# atmega_fusebit_doctor_V2hOld.net
KiCad netlist of a schematic drawn in EAGLE
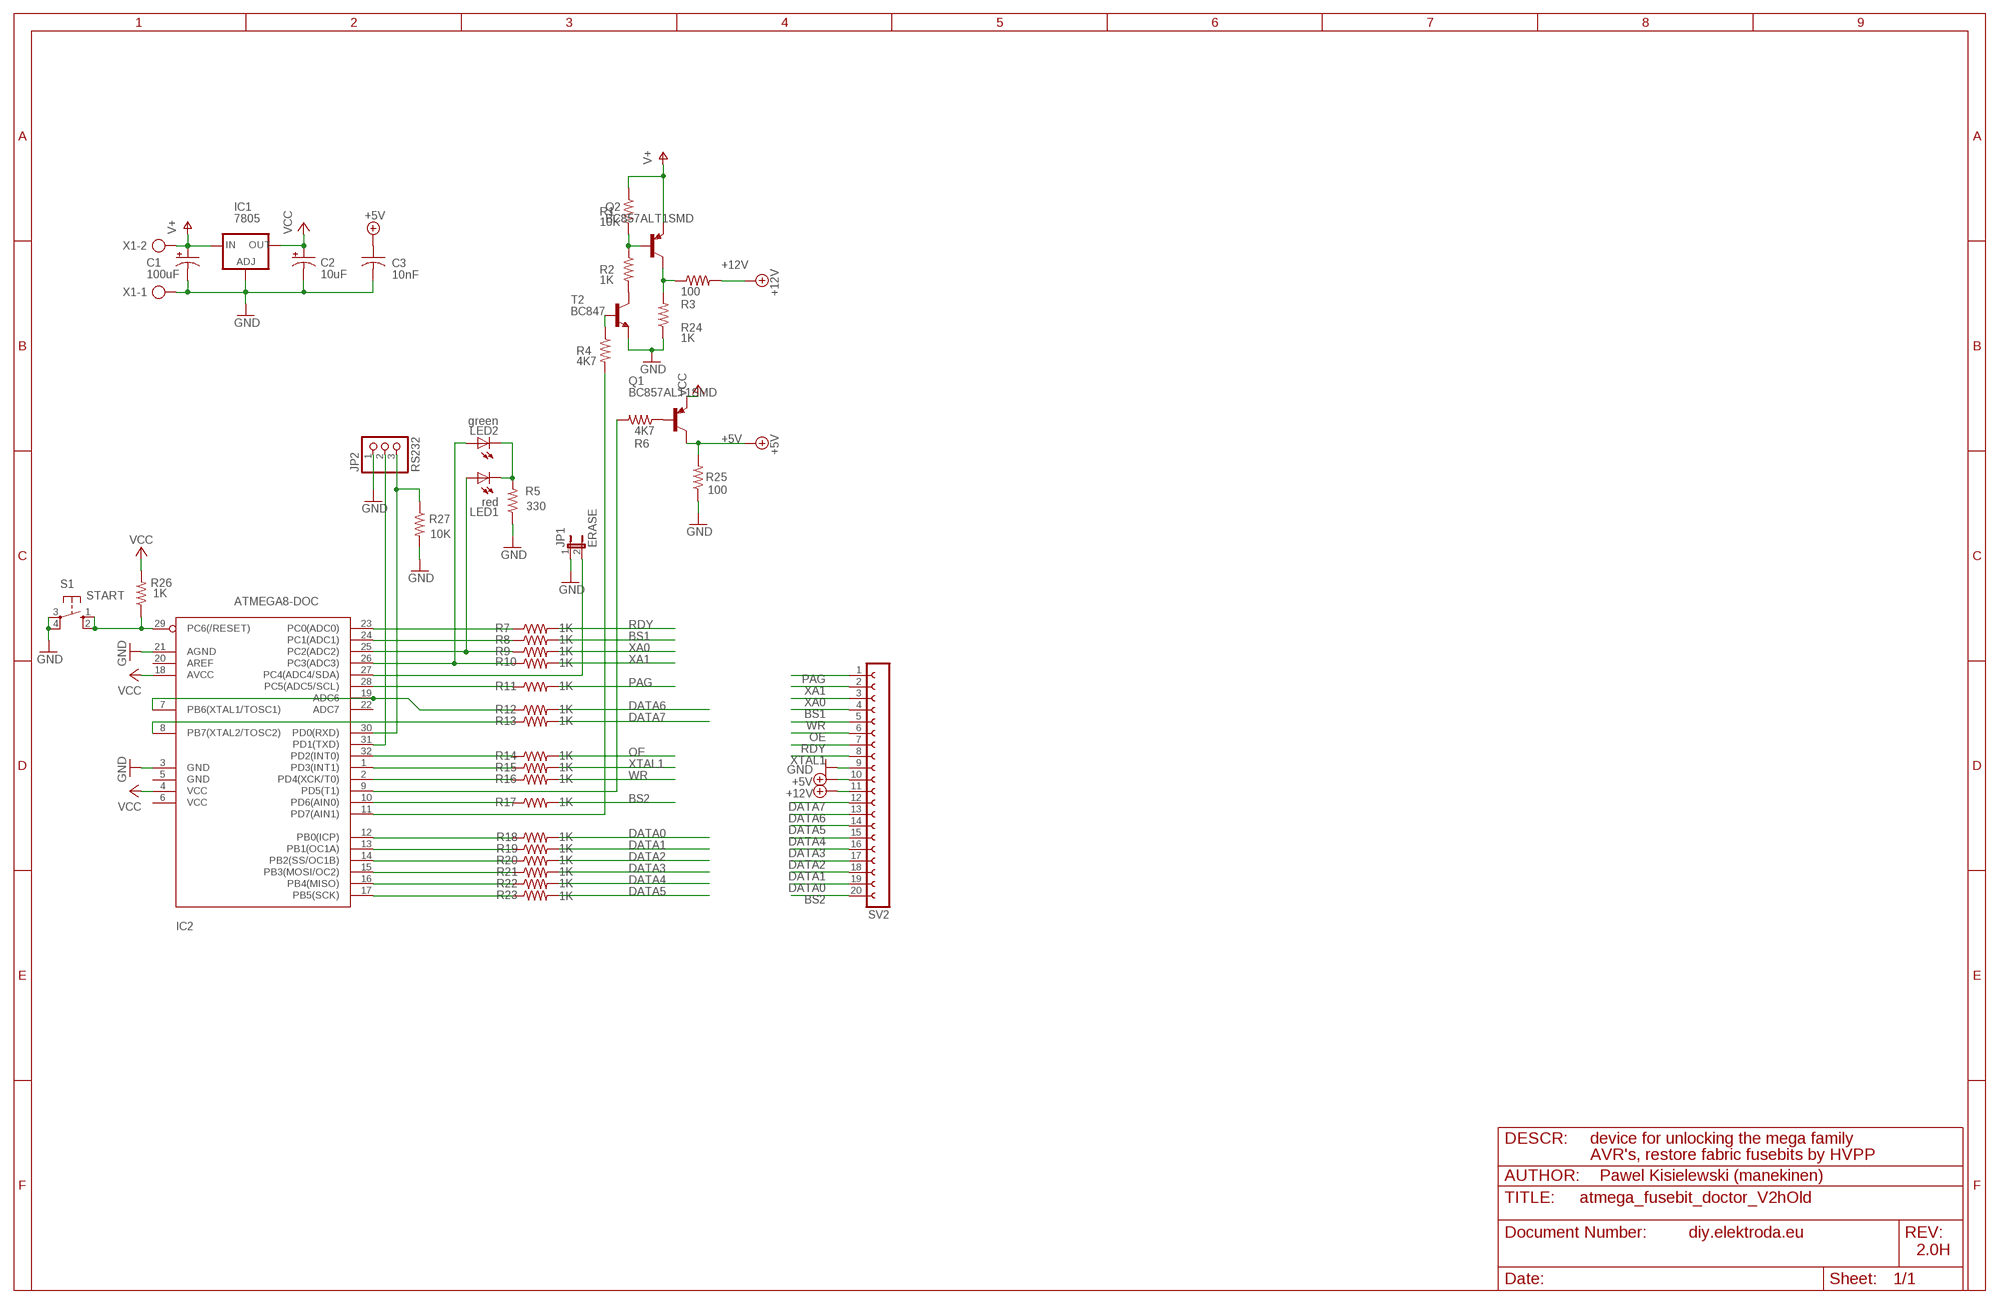
[diagram p0: schematic, sheet 1]

(export (version "E")
  (design (tool "Eeschema 10.0.6"))
  (components
    (comp (ref "C1")
      (value "100uF")
      (footprint "eagle-import:EIA3216")
      (libsource (lib "eagle-import") (part "CAP_POL1206"))
    )
    (comp (ref "C2")
      (value "10uF")
      (footprint "eagle-import:EIA3216")
      (libsource (lib "eagle-import") (part "CAP_POL1206"))
    )
    (comp (ref "C3")
      (value "10nF")
      (footprint "eagle-import:C0805")
      (libsource (lib "eagle-import") (part "C-USC0805"))
    )
    (comp (ref "IC1")
      (value "7805")
      (footprint "eagle-import:V-REG_DPACK")
      (libsource (lib "eagle-import") (part "V_REG_317DPACK"))
    )
    (comp (ref "IC2")
      (value "ATMEGA8-DOC")
      (footprint "eagle-import:TQFP32-08")
      (libsource (lib "eagle-import") (part "AVR-MEGA8-AI"))
    )
    (comp (ref "JP1")
      (value "ERASE")
      (footprint "eagle-import:JP1")
      (libsource (lib "eagle-import") (part "JP1E"))
    )
    (comp (ref "JP2")
      (value "RS232")
      (footprint "eagle-import:1X03")
      (libsource (lib "eagle-import") (part "PINHD-1X3"))
    )
    (comp (ref "LED1")
      (value "red")
      (footprint "eagle-import:SML0603")
      (libsource (lib "eagle-import") (part "LEDSML0603"))
    )
    (comp (ref "LED2")
      (value "green")
      (footprint "eagle-import:SML0603")
      (libsource (lib "eagle-import") (part "LEDSML0603"))
    )
    (comp (ref "Q1")
      (value "BC857ALT1SMD")
      (footprint "eagle-import:SOT23-BEC")
      (libsource (lib "eagle-import") (part "BC857SMDALT1"))
    )
    (comp (ref "Q2")
      (value "BC857ALT1SMD")
      (footprint "eagle-import:SOT23-BEC")
      (libsource (lib "eagle-import") (part "BC857SMDALT1"))
    )
    (comp (ref "R1")
      (value "10K")
      (footprint "eagle-import:R0805")
      (libsource (lib "eagle-import") (part "R-US_R0805"))
    )
    (comp (ref "R2")
      (value "1K")
      (footprint "eagle-import:R0805")
      (libsource (lib "eagle-import") (part "R-US_R0805"))
    )
    (comp (ref "R3")
      (value "100")
      (footprint "eagle-import:R0805")
      (libsource (lib "eagle-import") (part "R-US_R0805"))
    )
    (comp (ref "R4")
      (value "4K7")
      (footprint "eagle-import:R0805")
      (libsource (lib "eagle-import") (part "R-US_R0805"))
    )
    (comp (ref "R5")
      (value "330")
      (footprint "eagle-import:R0805")
      (libsource (lib "eagle-import") (part "R-US_R0805"))
    )
    (comp (ref "R6")
      (value "4K7")
      (footprint "eagle-import:R0805")
      (libsource (lib "eagle-import") (part "R-US_R0805"))
    )
    (comp (ref "R7")
      (value "1K")
      (footprint "eagle-import:R0805")
      (libsource (lib "eagle-import") (part "R-US_R0805"))
    )
    (comp (ref "R8")
      (value "1K")
      (footprint "eagle-import:R0805")
      (libsource (lib "eagle-import") (part "R-US_R0805"))
    )
    (comp (ref "R9")
      (value "1K")
      (footprint "eagle-import:R0805")
      (libsource (lib "eagle-import") (part "R-US_R0805"))
    )
    (comp (ref "R10")
      (value "1K")
      (footprint "eagle-import:R0805")
      (libsource (lib "eagle-import") (part "R-US_R0805"))
    )
    (comp (ref "R11")
      (value "1K")
      (footprint "eagle-import:R0805")
      (libsource (lib "eagle-import") (part "R-US_R0805"))
    )
    (comp (ref "R12")
      (value "1K")
      (footprint "eagle-import:R0805")
      (libsource (lib "eagle-import") (part "R-US_R0805"))
    )
    (comp (ref "R13")
      (value "1K")
      (footprint "eagle-import:R0805")
      (libsource (lib "eagle-import") (part "R-US_R0805"))
    )
    (comp (ref "R14")
      (value "1K")
      (footprint "eagle-import:R0805")
      (libsource (lib "eagle-import") (part "R-US_R0805"))
    )
    (comp (ref "R15")
      (value "1K")
      (footprint "eagle-import:R0805")
      (libsource (lib "eagle-import") (part "R-US_R0805"))
    )
    (comp (ref "R16")
      (value "1K")
      (footprint "eagle-import:R0805")
      (libsource (lib "eagle-import") (part "R-US_R0805"))
    )
    (comp (ref "R17")
      (value "1K")
      (footprint "eagle-import:R0805")
      (libsource (lib "eagle-import") (part "R-US_R0805"))
    )
    (comp (ref "R18")
      (value "1K")
      (footprint "eagle-import:R0805")
      (libsource (lib "eagle-import") (part "R-US_R0805"))
    )
    (comp (ref "R19")
      (value "1K")
      (footprint "eagle-import:R0805")
      (libsource (lib "eagle-import") (part "R-US_R0805"))
    )
    (comp (ref "R20")
      (value "1K")
      (footprint "eagle-import:R0805")
      (libsource (lib "eagle-import") (part "R-US_R0805"))
    )
    (comp (ref "R21")
      (value "1K")
      (footprint "eagle-import:R0805")
      (libsource (lib "eagle-import") (part "R-US_R0805"))
    )
    (comp (ref "R22")
      (value "1K")
      (footprint "eagle-import:R0805")
      (libsource (lib "eagle-import") (part "R-US_R0805"))
    )
    (comp (ref "R23")
      (value "1K")
      (footprint "eagle-import:R0805")
      (libsource (lib "eagle-import") (part "R-US_R0805"))
    )
    (comp (ref "R24")
      (value "1K")
      (footprint "eagle-import:R0805")
      (libsource (lib "eagle-import") (part "R-US_R0805"))
    )
    (comp (ref "R25")
      (value "100")
      (footprint "eagle-import:R0805")
      (libsource (lib "eagle-import") (part "R-US_R0805"))
    )
    (comp (ref "R26")
      (value "1K")
      (footprint "eagle-import:R0805")
      (libsource (lib "eagle-import") (part "R-US_R0805"))
    )
    (comp (ref "R27")
      (value "10K")
      (footprint "eagle-import:R0805")
      (libsource (lib "eagle-import") (part "R-US_R0805"))
    )
    (comp (ref "S1")
      (value "START")
      (footprint "eagle-import:B3F-10XX")
      (libsource (lib "eagle-import") (part "10-XX"))
    )
    (comp (ref "SV2")
      (value "FE20-1")
      (footprint "eagle-import:FE20")
      (libsource (lib "eagle-import") (part "FE20-1"))
    )
    (comp (ref "T2")
      (value "BC847")
      (footprint "eagle-import:SOT23")
      (libsource (lib "eagle-import") (part "BC847"))
    )
    (comp (ref "X1")
      (value "AK500/2")
      (footprint "eagle-import:AK500_2")
      (libsource (lib "eagle-import") (part "AK500/2"))
    )
  )
  (nets
    (net (code "1") (name "+5V") (class "Default")
      (node (ref "C3") (pin "1") (pinfunction "1_1") (pintype "passive"))
      (node (ref "Q1") (pin "C") (pinfunction "C_C") (pintype "passive"))
      (node (ref "R25") (pin "2") (pinfunction "2_2") (pintype "passive"))
      (node (ref "SV2") (pin "10") (pinfunction "10_10") (pintype "passive"))
    )
    (net (code "2") (name "+12V") (class "Default")
      (node (ref "R3") (pin "2") (pinfunction "2_2") (pintype "passive"))
      (node (ref "SV2") (pin "11") (pinfunction "11_11") (pintype "passive"))
    )
    (net (code "3") (name "/BS1") (class "Default")
      (node (ref "R8") (pin "2") (pinfunction "2_2") (pintype "passive"))
      (node (ref "SV2") (pin "4") (pinfunction "4_4") (pintype "passive"))
    )
    (net (code "4") (name "/BS2") (class "Default")
      (node (ref "R17") (pin "2") (pinfunction "2_2") (pintype "passive"))
      (node (ref "SV2") (pin "20") (pinfunction "20_20") (pintype "passive"))
    )
    (net (code "5") (name "/DATA0") (class "Default")
      (node (ref "R18") (pin "2") (pinfunction "2_2") (pintype "passive"))
      (node (ref "SV2") (pin "19") (pinfunction "19_19") (pintype "passive"))
    )
    (net (code "6") (name "/DATA1") (class "Default")
      (node (ref "R19") (pin "2") (pinfunction "2_2") (pintype "passive"))
      (node (ref "SV2") (pin "18") (pinfunction "18_18") (pintype "passive"))
    )
    (net (code "7") (name "/DATA2") (class "Default")
      (node (ref "R20") (pin "2") (pinfunction "2_2") (pintype "passive"))
      (node (ref "SV2") (pin "17") (pinfunction "17_17") (pintype "passive"))
    )
    (net (code "8") (name "/DATA3") (class "Default")
      (node (ref "R21") (pin "2") (pinfunction "2_2") (pintype "passive"))
      (node (ref "SV2") (pin "16") (pinfunction "16_16") (pintype "passive"))
    )
    (net (code "9") (name "/DATA4") (class "Default")
      (node (ref "R22") (pin "2") (pinfunction "2_2") (pintype "passive"))
      (node (ref "SV2") (pin "15") (pinfunction "15_15") (pintype "passive"))
    )
    (net (code "10") (name "/DATA5") (class "Default")
      (node (ref "R23") (pin "2") (pinfunction "2_2") (pintype "passive"))
      (node (ref "SV2") (pin "14") (pinfunction "14_14") (pintype "passive"))
    )
    (net (code "11") (name "/DATA6") (class "Default")
      (node (ref "R12") (pin "2") (pinfunction "2_2") (pintype "passive"))
      (node (ref "SV2") (pin "13") (pinfunction "13_13") (pintype "passive"))
    )
    (net (code "12") (name "/DATA7") (class "Default")
      (node (ref "R13") (pin "2") (pinfunction "2_2") (pintype "passive"))
      (node (ref "SV2") (pin "12") (pinfunction "12_12") (pintype "passive"))
    )
    (net (code "13") (name "/OE") (class "Default")
      (node (ref "R14") (pin "2") (pinfunction "2_2") (pintype "passive"))
      (node (ref "SV2") (pin "6") (pinfunction "6_6") (pintype "passive"))
    )
    (net (code "14") (name "/PAG") (class "Default")
      (node (ref "R11") (pin "2") (pinfunction "2_2") (pintype "passive"))
      (node (ref "SV2") (pin "1") (pinfunction "1_1") (pintype "passive"))
    )
    (net (code "15") (name "/RDY") (class "Default")
      (node (ref "R7") (pin "2") (pinfunction "2_2") (pintype "passive"))
      (node (ref "SV2") (pin "7") (pinfunction "7_7") (pintype "passive"))
    )
    (net (code "16") (name "/WR") (class "Default")
      (node (ref "R16") (pin "2") (pinfunction "2_2") (pintype "passive"))
      (node (ref "SV2") (pin "5") (pinfunction "5_5") (pintype "passive"))
    )
    (net (code "17") (name "/XA0") (class "Default")
      (node (ref "R9") (pin "2") (pinfunction "2_2") (pintype "passive"))
      (node (ref "SV2") (pin "3") (pinfunction "3_3") (pintype "passive"))
    )
    (net (code "18") (name "/XA1") (class "Default")
      (node (ref "R10") (pin "2") (pinfunction "2_2") (pintype "passive"))
      (node (ref "SV2") (pin "2") (pinfunction "2_2") (pintype "passive"))
    )
    (net (code "19") (name "/XTAL1") (class "Default")
      (node (ref "R15") (pin "2") (pinfunction "2_2") (pintype "passive"))
      (node (ref "SV2") (pin "8") (pinfunction "8_8") (pintype "passive"))
    )
    (net (code "20") (name "GND") (class "Default")
      (node (ref "C1") (pin "C") (pinfunction "-_C") (pintype "passive"))
      (node (ref "C2") (pin "C") (pinfunction "-_C") (pintype "passive"))
      (node (ref "C3") (pin "2") (pinfunction "2_2") (pintype "passive"))
      (node (ref "IC1") (pin "1") (pinfunction "ADJ_1") (pintype "input"))
      (node (ref "IC2") (pin "21") (pinfunction "AGND_21") (pintype "bidirectional"))
      (node (ref "IC2") (pin "3") (pinfunction "GND_3") (pintype "bidirectional"))
      (node (ref "JP1") (pin "1") (pinfunction "1_1") (pintype "passive"))
      (node (ref "JP2") (pin "1") (pinfunction "1_1") (pintype "passive"))
      (node (ref "R24") (pin "1") (pinfunction "1_1") (pintype "passive"))
      (node (ref "R25") (pin "1") (pinfunction "1_1") (pintype "passive"))
      (node (ref "R27") (pin "2") (pinfunction "2_2") (pintype "passive"))
      (node (ref "R5") (pin "1") (pinfunction "1_1") (pintype "passive"))
      (node (ref "S1") (pin "3") (pinfunction "P_3") (pintype "passive"))
      (node (ref "S1") (pin "4") (pinfunction "P1_4") (pintype "passive"))
      (node (ref "SV2") (pin "9") (pinfunction "9_9") (pintype "passive"))
      (node (ref "T2") (pin "2") (pinfunction "E_2") (pintype "passive"))
      (node (ref "X1") (pin "1") (pinfunction "KL_1") (pintype "passive"))
    )
    (net (code "21") (name "Net-(IC2-ADC6)") (class "Default")
      (node (ref "IC2") (pin "19") (pinfunction "ADC6_19") (pintype "bidirectional"))
      (node (ref "IC2") (pin "7") (pinfunction "PB6(XTAL1/TOSC1)_7") (pintype "bidirectional"))
      (node (ref "R12") (pin "1") (pinfunction "1_1") (pintype "passive"))
    )
    (net (code "22") (name "Net-(IC2-PB0(ICP))") (class "Default")
      (node (ref "IC2") (pin "12") (pinfunction "PB0(ICP)_12") (pintype "bidirectional"))
      (node (ref "R18") (pin "1") (pinfunction "1_1") (pintype "passive"))
    )
    (net (code "23") (name "Net-(IC2-PB1(OC1A))") (class "Default")
      (node (ref "IC2") (pin "13") (pinfunction "PB1(OC1A)_13") (pintype "bidirectional"))
      (node (ref "R19") (pin "1") (pinfunction "1_1") (pintype "passive"))
    )
    (net (code "24") (name "Net-(IC2-PB2(SS{slash}OC1B))") (class "Default")
      (node (ref "IC2") (pin "14") (pinfunction "PB2(SS/OC1B)_14") (pintype "bidirectional"))
      (node (ref "R20") (pin "1") (pinfunction "1_1") (pintype "passive"))
    )
    (net (code "25") (name "Net-(IC2-PB3(MOSI{slash}OC2))") (class "Default")
      (node (ref "IC2") (pin "15") (pinfunction "PB3(MOSI/OC2)_15") (pintype "bidirectional"))
      (node (ref "R21") (pin "1") (pinfunction "1_1") (pintype "passive"))
    )
    (net (code "26") (name "Net-(IC2-PB4(MISO))") (class "Default")
      (node (ref "IC2") (pin "16") (pinfunction "PB4(MISO)_16") (pintype "bidirectional"))
      (node (ref "R22") (pin "1") (pinfunction "1_1") (pintype "passive"))
    )
    (net (code "27") (name "Net-(IC2-PB5(SCK))") (class "Default")
      (node (ref "IC2") (pin "17") (pinfunction "PB5(SCK)_17") (pintype "bidirectional"))
      (node (ref "R23") (pin "1") (pinfunction "1_1") (pintype "passive"))
    )
    (net (code "28") (name "Net-(IC2-PB7(XTAL2{slash}TOSC2))") (class "Default")
      (node (ref "IC2") (pin "8") (pinfunction "PB7(XTAL2/TOSC2)_8") (pintype "bidirectional"))
      (node (ref "R13") (pin "1") (pinfunction "1_1") (pintype "passive"))
    )
    (net (code "29") (name "Net-(IC2-PC0(ADC0))") (class "Default")
      (node (ref "IC2") (pin "23") (pinfunction "PC0(ADC0)_23") (pintype "bidirectional"))
      (node (ref "R7") (pin "1") (pinfunction "1_1") (pintype "passive"))
    )
    (net (code "30") (name "Net-(IC2-PC1(ADC1))") (class "Default")
      (node (ref "IC2") (pin "24") (pinfunction "PC1(ADC1)_24") (pintype "bidirectional"))
      (node (ref "R8") (pin "1") (pinfunction "1_1") (pintype "passive"))
    )
    (net (code "31") (name "Net-(IC2-PC2(ADC2))") (class "Default")
      (node (ref "IC2") (pin "25") (pinfunction "PC2(ADC2)_25") (pintype "bidirectional"))
      (node (ref "LED1") (pin "A") (pinfunction "A_A") (pintype "passive"))
      (node (ref "R9") (pin "1") (pinfunction "1_1") (pintype "passive"))
    )
    (net (code "32") (name "Net-(IC2-PC3(ADC3))") (class "Default")
      (node (ref "IC2") (pin "26") (pinfunction "PC3(ADC3)_26") (pintype "bidirectional"))
      (node (ref "LED2") (pin "A") (pinfunction "A_A") (pintype "passive"))
      (node (ref "R10") (pin "1") (pinfunction "1_1") (pintype "passive"))
    )
    (net (code "33") (name "Net-(IC2-PC4(ADC4{slash}SDA))") (class "Default")
      (node (ref "IC2") (pin "27") (pinfunction "PC4(ADC4/SDA)_27") (pintype "bidirectional"))
      (node (ref "JP1") (pin "2") (pinfunction "2_2") (pintype "passive"))
    )
    (net (code "34") (name "Net-(IC2-PC5(ADC5{slash}SCL))") (class "Default")
      (node (ref "IC2") (pin "28") (pinfunction "PC5(ADC5/SCL)_28") (pintype "bidirectional"))
      (node (ref "R11") (pin "1") (pinfunction "1_1") (pintype "passive"))
    )
    (net (code "35") (name "Net-(IC2-PC6({slash}RESET))") (class "Default")
      (node (ref "IC2") (pin "29") (pinfunction "PC6(/RESET)_29") (pintype "bidirectional"))
      (node (ref "R26") (pin "1") (pinfunction "1_1") (pintype "passive"))
      (node (ref "S1") (pin "1") (pinfunction "S_1") (pintype "passive"))
      (node (ref "S1") (pin "2") (pinfunction "S1_2") (pintype "passive"))
    )
    (net (code "36") (name "Net-(IC2-PD0(RXD))") (class "Default")
      (node (ref "IC2") (pin "30") (pinfunction "PD0(RXD)_30") (pintype "bidirectional"))
      (node (ref "JP2") (pin "3") (pinfunction "3_3") (pintype "passive"))
      (node (ref "R27") (pin "1") (pinfunction "1_1") (pintype "passive"))
    )
    (net (code "37") (name "Net-(IC2-PD1(TXD))") (class "Default")
      (node (ref "IC2") (pin "31") (pinfunction "PD1(TXD)_31") (pintype "bidirectional"))
      (node (ref "JP2") (pin "2") (pinfunction "2_2") (pintype "passive"))
    )
    (net (code "38") (name "Net-(IC2-PD2(INT0))") (class "Default")
      (node (ref "IC2") (pin "32") (pinfunction "PD2(INT0)_32") (pintype "bidirectional"))
      (node (ref "R14") (pin "1") (pinfunction "1_1") (pintype "passive"))
    )
    (net (code "39") (name "Net-(IC2-PD3(INT1))") (class "Default")
      (node (ref "IC2") (pin "1") (pinfunction "PD3(INT1)_1") (pintype "bidirectional"))
      (node (ref "R15") (pin "1") (pinfunction "1_1") (pintype "passive"))
    )
    (net (code "40") (name "Net-(IC2-PD4(XCK{slash}T0))") (class "Default")
      (node (ref "IC2") (pin "2") (pinfunction "PD4(XCK/T0)_2") (pintype "bidirectional"))
      (node (ref "R16") (pin "1") (pinfunction "1_1") (pintype "passive"))
    )
    (net (code "41") (name "Net-(IC2-PD5(T1))") (class "Default")
      (node (ref "IC2") (pin "9") (pinfunction "PD5(T1)_9") (pintype "bidirectional"))
      (node (ref "R6") (pin "2") (pinfunction "2_2") (pintype "passive"))
    )
    (net (code "42") (name "Net-(IC2-PD6(AIN0))") (class "Default")
      (node (ref "IC2") (pin "10") (pinfunction "PD6(AIN0)_10") (pintype "bidirectional"))
      (node (ref "R17") (pin "1") (pinfunction "1_1") (pintype "passive"))
    )
    (net (code "43") (name "Net-(IC2-PD7(AIN1))") (class "Default")
      (node (ref "IC2") (pin "11") (pinfunction "PD7(AIN1)_11") (pintype "bidirectional"))
      (node (ref "R4") (pin "2") (pinfunction "2_2") (pintype "passive"))
    )
    (net (code "44") (name "Net-(LED1-PadC)") (class "Default")
      (node (ref "LED1") (pin "C") (pinfunction "C_C") (pintype "passive"))
      (node (ref "LED2") (pin "C") (pinfunction "C_C") (pintype "passive"))
      (node (ref "R5") (pin "2") (pinfunction "2_2") (pintype "passive"))
    )
    (net (code "45") (name "Net-(Q1-PadB)") (class "Default")
      (node (ref "Q1") (pin "B") (pinfunction "B_B") (pintype "passive"))
      (node (ref "R6") (pin "1") (pinfunction "1_1") (pintype "passive"))
    )
    (net (code "46") (name "Net-(Q2-PadB)") (class "Default")
      (node (ref "Q2") (pin "B") (pinfunction "B_B") (pintype "passive"))
      (node (ref "R1") (pin "2") (pinfunction "2_2") (pintype "passive"))
      (node (ref "R2") (pin "1") (pinfunction "1_1") (pintype "passive"))
    )
    (net (code "47") (name "Net-(Q2-PadC)") (class "Default")
      (node (ref "Q2") (pin "C") (pinfunction "C_C") (pintype "passive"))
      (node (ref "R24") (pin "2") (pinfunction "2_2") (pintype "passive"))
      (node (ref "R3") (pin "1") (pinfunction "1_1") (pintype "passive"))
    )
    (net (code "48") (name "Net-(T2-B)") (class "Default")
      (node (ref "R4") (pin "1") (pinfunction "1_1") (pintype "passive"))
      (node (ref "T2") (pin "1") (pinfunction "B_1") (pintype "passive"))
    )
    (net (code "49") (name "Net-(T2-C)") (class "Default")
      (node (ref "R2") (pin "2") (pinfunction "2_2") (pintype "passive"))
      (node (ref "T2") (pin "3") (pinfunction "C_3") (pintype "passive"))
    )
    (net (code "50") (name "V+") (class "Default")
      (node (ref "C1") (pin "A") (pinfunction "+_A") (pintype "passive"))
      (node (ref "IC1") (pin "3") (pinfunction "IN_3") (pintype "input"))
      (node (ref "Q2") (pin "E") (pinfunction "E_E") (pintype "passive"))
      (node (ref "R1") (pin "1") (pinfunction "1_1") (pintype "passive"))
      (node (ref "X1") (pin "2") (pinfunction "KL_2") (pintype "passive"))
    )
    (net (code "51") (name "VCC") (class "Default")
      (node (ref "C2") (pin "A") (pinfunction "+_A") (pintype "passive"))
      (node (ref "IC1") (pin "4") (pinfunction "OUT_4") (pintype "output"))
      (node (ref "IC2") (pin "18") (pinfunction "AVCC_18") (pintype "bidirectional"))
      (node (ref "IC2") (pin "4") (pinfunction "VCC_4") (pintype "bidirectional"))
      (node (ref "Q1") (pin "E") (pinfunction "E_E") (pintype "passive"))
      (node (ref "R26") (pin "2") (pinfunction "2_2") (pintype "passive"))
    )
    (net (code "52") (name "unconnected-(IC2-ADC7-Pad22)") (class "Default")
      (node (ref "IC2") (pin "22") (pinfunction "ADC7_22") (pintype "bidirectional"))
    )
    (net (code "53") (name "unconnected-(IC2-AREF-Pad20)") (class "Default")
      (node (ref "IC2") (pin "20") (pinfunction "AREF_20") (pintype "bidirectional"))
    )
    (net (code "54") (name "unconnected-(IC2-GND-Pad5)") (class "Default")
      (node (ref "IC2") (pin "5") (pinfunction "GND_5") (pintype "bidirectional"))
    )
    (net (code "55") (name "unconnected-(IC2-VCC-Pad6)") (class "Default")
      (node (ref "IC2") (pin "6") (pinfunction "VCC_6") (pintype "bidirectional"))
    )
  )
)
